# MaTouch_Devkit_Stepper_Driver_V1_1.net
KiCad netlist of a schematic drawn in EAGLE
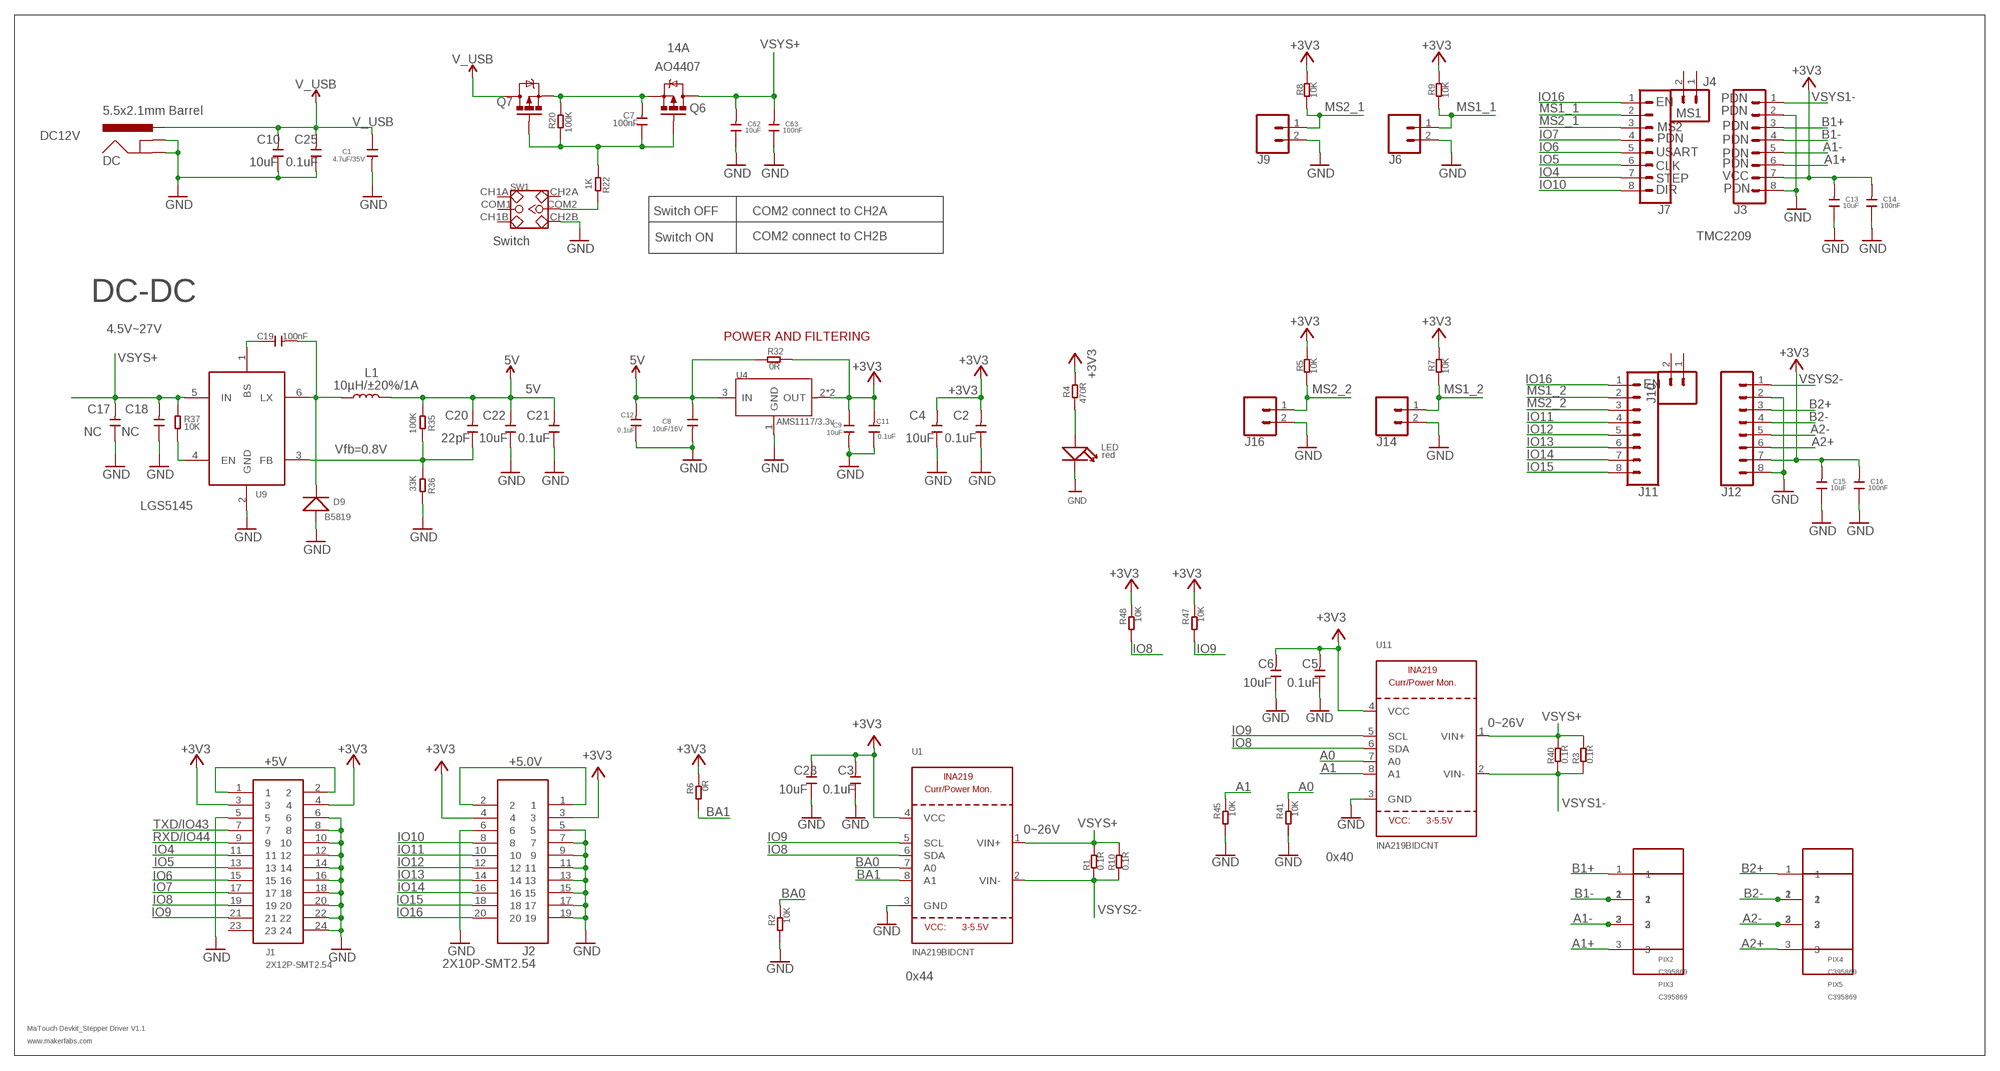
[diagram p0: schematic, sheet 1]

(export (version "E")
  (design (tool "Eeschema 10.0.6"))
  (components
    (comp (ref "C1")
      (value "4.7uF/35V")
      (footprint "eagle-import:0603")
      (libsource (lib "eagle-import") (part "C-0603"))
    )
    (comp (ref "C2")
      (value "0.1uF")
      (footprint "eagle-import:0603")
      (libsource (lib "eagle-import") (part "C-0603"))
    )
    (comp (ref "C3")
      (value "0.1uF")
      (footprint "eagle-import:0603")
      (libsource (lib "eagle-import") (part "C-0603"))
    )
    (comp (ref "C4")
      (value "10uF")
      (footprint "eagle-import:0603")
      (libsource (lib "eagle-import") (part "C-0603"))
    )
    (comp (ref "C5")
      (value "0.1uF")
      (footprint "eagle-import:0603")
      (libsource (lib "eagle-import") (part "C-0603"))
    )
    (comp (ref "C6")
      (value "10uF")
      (footprint "eagle-import:0603")
      (libsource (lib "eagle-import") (part "C-0603"))
    )
    (comp (ref "C7")
      (value "100nF")
      (footprint "eagle-import:0603")
      (libsource (lib "eagle-import") (part "C-0603"))
    )
    (comp (ref "C8")
      (value "10uF/16V")
      (footprint "eagle-import:0603")
      (libsource (lib "eagle-import") (part "C-0603"))
    )
    (comp (ref "C9")
      (value "10uF")
      (footprint "eagle-import:0603")
      (libsource (lib "eagle-import") (part "C-0603"))
    )
    (comp (ref "C10")
      (value "10uF")
      (footprint "eagle-import:0603")
      (libsource (lib "eagle-import") (part "C-0603"))
    )
    (comp (ref "C11")
      (value "0.1uF")
      (footprint "eagle-import:0603")
      (libsource (lib "eagle-import") (part "C-0603"))
    )
    (comp (ref "C12")
      (value "0.1uF")
      (footprint "eagle-import:0603")
      (libsource (lib "eagle-import") (part "C-0603"))
    )
    (comp (ref "C13")
      (value "10uF")
      (footprint "eagle-import:0603")
      (libsource (lib "eagle-import") (part "C-0603"))
    )
    (comp (ref "C14")
      (value "100nF")
      (footprint "eagle-import:0603")
      (libsource (lib "eagle-import") (part "C-0603"))
    )
    (comp (ref "C15")
      (value "10uF")
      (footprint "eagle-import:0603")
      (libsource (lib "eagle-import") (part "C-0603"))
    )
    (comp (ref "C16")
      (value "100nF")
      (footprint "eagle-import:0603")
      (libsource (lib "eagle-import") (part "C-0603"))
    )
    (comp (ref "C17")
      (value "NC")
      (footprint "eagle-import:0603")
      (libsource (lib "eagle-import") (part "C-0603"))
    )
    (comp (ref "C18")
      (value "NC")
      (footprint "eagle-import:0603")
      (libsource (lib "eagle-import") (part "C-0603"))
    )
    (comp (ref "C19")
      (value "100nF")
      (footprint "eagle-import:0603")
      (libsource (lib "eagle-import") (part "C-0603"))
    )
    (comp (ref "C20")
      (value "22pF")
      (footprint "eagle-import:0603")
      (libsource (lib "eagle-import") (part "C-0603"))
    )
    (comp (ref "C21")
      (value "0.1uF")
      (footprint "eagle-import:0603")
      (libsource (lib "eagle-import") (part "C-0603"))
    )
    (comp (ref "C22")
      (value "10uF")
      (footprint "eagle-import:0603")
      (libsource (lib "eagle-import") (part "C-0603"))
    )
    (comp (ref "C23")
      (value "10uF")
      (footprint "eagle-import:0603")
      (libsource (lib "eagle-import") (part "C-0603"))
    )
    (comp (ref "C25")
      (value "0.1uF")
      (footprint "eagle-import:0603")
      (libsource (lib "eagle-import") (part "C-0603"))
    )
    (comp (ref "C62")
      (value "10uF")
      (footprint "eagle-import:0603")
      (libsource (lib "eagle-import") (part "C-0603"))
    )
    (comp (ref "C63")
      (value "100nF")
      (footprint "eagle-import:0603")
      (libsource (lib "eagle-import") (part "C-0603"))
    )
    (comp (ref "D9")
      (value "B5819")
      (footprint "eagle-import:SOD123")
      (libsource (lib "eagle-import") (part "D'1206'"))
    )
    (comp (ref "DC")
      (value "5.5x2.1mm Barrel")
      (footprint "eagle-import:POWER_JACK_SMD")
      (libsource (lib "eagle-import") (part "POWER_JACKSMD"))
    )
    (comp (ref "J1")
      (value "2X12P-SMT2.54")
      (footprint "eagle-import:2X12P-SMT2.54")
      (libsource (lib "eagle-import") (part "2X12P-SMT2.54"))
    )
    (comp (ref "J2")
      (value "2X10P-SMT2.54")
      (footprint "eagle-import:2X10P-SMT2.54")
      (libsource (lib "eagle-import") (part "2X10P-SMT2.54"))
    )
    (comp (ref "J3")
      (value "CONN_08\"")
      (footprint "eagle-import:1X08")
      (fields (field (name "PROD_ID") "CONN-08438"))
      (libsource (lib "eagle-import") (part "CONN_08{dblquote}"))
    )
    (comp (ref "J4")
      (value "CONN_02LOCK")
      (footprint "eagle-import:1X02_LOCK")
      (libsource (lib "eagle-import") (part "CONN_02LOCK"))
    )
    (comp (ref "J6")
      (value "CONN_02LOCK")
      (footprint "eagle-import:1X02_LOCK")
      (libsource (lib "eagle-import") (part "CONN_02LOCK"))
    )
    (comp (ref "J7")
      (value "CONN_08\"")
      (footprint "eagle-import:1X08")
      (libsource (lib "eagle-import") (part "CONN_08{dblquote}"))
    )
    (comp (ref "J9")
      (value "CONN_02LOCK")
      (footprint "eagle-import:1X02_LOCK")
      (libsource (lib "eagle-import") (part "CONN_02LOCK"))
    )
    (comp (ref "J10")
      (value "CONN_02LOCK")
      (footprint "eagle-import:1X02_LOCK")
      (libsource (lib "eagle-import") (part "CONN_02LOCK"))
    )
    (comp (ref "J11")
      (value "CONN_08\"")
      (footprint "eagle-import:1X08")
      (libsource (lib "eagle-import") (part "CONN_08{dblquote}"))
    )
    (comp (ref "J12")
      (value "CONN_08\"")
      (footprint "eagle-import:1X08")
      (fields (field (name "PROD_ID") "CONN-08438"))
      (libsource (lib "eagle-import") (part "CONN_08{dblquote}"))
    )
    (comp (ref "J14")
      (value "CONN_02LOCK")
      (footprint "eagle-import:1X02_LOCK")
      (libsource (lib "eagle-import") (part "CONN_02LOCK"))
    )
    (comp (ref "J16")
      (value "CONN_02LOCK")
      (footprint "eagle-import:1X02_LOCK")
      (libsource (lib "eagle-import") (part "CONN_02LOCK"))
    )
    (comp (ref "L1")
      (value "10µH/±20%/1A")
      (footprint "eagle-import:SRN6045")
      (libsource (lib "eagle-import") (part "INDUCTOR-SRN6045-33UH"))
    )
    (comp (ref "LED")
      (value "red")
      (footprint "eagle-import:DISCRETE_LED-0603")
      (libsource (lib "eagle-import") (part "DISCRETE_LED0603"))
    )
    (comp (ref "PIX2")
      (value "C395869")
      (footprint "eagle-import:PIN_3P")
      (libsource (lib "eagle-import") (part "C395869"))
    )
    (comp (ref "PIX3")
      (value "C395869")
      (footprint "eagle-import:PIN_3P")
      (libsource (lib "eagle-import") (part "C395869"))
    )
    (comp (ref "PIX4")
      (value "C395869")
      (footprint "eagle-import:PIN_3P")
      (libsource (lib "eagle-import") (part "C395869"))
    )
    (comp (ref "PIX5")
      (value "C395869")
      (footprint "eagle-import:PIN_3P")
      (libsource (lib "eagle-import") (part "C395869"))
    )
    (comp (ref "Q6")
      (value "MOSFET-PCHANNELFDS6675")
      (footprint "eagle-import:SO08")
      (libsource (lib "eagle-import") (part "MOSFET-PCHANNELFDS6675"))
    )
    (comp (ref "Q7")
      (value "MOSFET-PCHANNELFDS6675")
      (footprint "eagle-import:SO08")
      (libsource (lib "eagle-import") (part "MOSFET-PCHANNELFDS6675"))
    )
    (comp (ref "R1")
      (value "0.1R")
      (footprint "eagle-import:DISCRETE_R2512")
      (libsource (lib "eagle-import") (part "DISCRETE_R-2512"))
    )
    (comp (ref "R2")
      (value "10K")
      (footprint "eagle-import:R0603")
      (libsource (lib "eagle-import") (part "R-0603"))
    )
    (comp (ref "R3")
      (value "0.1R")
      (footprint "eagle-import:DISCRETE_R2512")
      (libsource (lib "eagle-import") (part "DISCRETE_R-2512"))
    )
    (comp (ref "R4")
      (value "470R")
      (footprint "eagle-import:R0603")
      (libsource (lib "eagle-import") (part "R-0603"))
    )
    (comp (ref "R5")
      (value "10K")
      (footprint "eagle-import:R0603")
      (libsource (lib "eagle-import") (part "R-0603"))
    )
    (comp (ref "R6")
      (value "0R")
      (footprint "eagle-import:R0603")
      (libsource (lib "eagle-import") (part "R-0603"))
    )
    (comp (ref "R7")
      (value "10K")
      (footprint "eagle-import:R0603")
      (libsource (lib "eagle-import") (part "R-0603"))
    )
    (comp (ref "R8")
      (value "10K")
      (footprint "eagle-import:R0603")
      (libsource (lib "eagle-import") (part "R-0603"))
    )
    (comp (ref "R9")
      (value "10K")
      (footprint "eagle-import:R0603")
      (libsource (lib "eagle-import") (part "R-0603"))
    )
    (comp (ref "R10")
      (value "0.1R")
      (footprint "eagle-import:DISCRETE_R2512")
      (libsource (lib "eagle-import") (part "DISCRETE_R-2512"))
    )
    (comp (ref "R20")
      (value "100K")
      (footprint "eagle-import:R0603")
      (libsource (lib "eagle-import") (part "R-0603"))
    )
    (comp (ref "R22")
      (value "1K")
      (footprint "eagle-import:R0603")
      (libsource (lib "eagle-import") (part "R-0603"))
    )
    (comp (ref "R32")
      (value "0R")
      (footprint "eagle-import:R0603")
      (libsource (lib "eagle-import") (part "R-0603"))
    )
    (comp (ref "R35")
      (value "100K")
      (footprint "eagle-import:R0603")
      (libsource (lib "eagle-import") (part "R-0603"))
    )
    (comp (ref "R36")
      (value "33K")
      (footprint "eagle-import:R0603")
      (libsource (lib "eagle-import") (part "R-0603"))
    )
    (comp (ref "R37")
      (value "10K")
      (footprint "eagle-import:R0603")
      (libsource (lib "eagle-import") (part "R-0603"))
    )
    (comp (ref "R40")
      (value "0.1R")
      (footprint "eagle-import:DISCRETE_R2512")
      (libsource (lib "eagle-import") (part "DISCRETE_R-2512"))
    )
    (comp (ref "R41")
      (value "10K")
      (footprint "eagle-import:R0603")
      (libsource (lib "eagle-import") (part "R-0603"))
    )
    (comp (ref "R45")
      (value "10K")
      (footprint "eagle-import:R0603")
      (libsource (lib "eagle-import") (part "R-0603"))
    )
    (comp (ref "R47")
      (value "10K")
      (footprint "eagle-import:R0603")
      (libsource (lib "eagle-import") (part "R-0603"))
    )
    (comp (ref "R48")
      (value "10K")
      (footprint "eagle-import:R0603")
      (libsource (lib "eagle-import") (part "R-0603"))
    )
    (comp (ref "SW1")
      (value "SWITCH-2CH-6P'90D'")
      (footprint "eagle-import:6P-2CH-2.54-9.0X3.6-90D")
      (libsource (lib "eagle-import") (part "SWITCH-2CH-6P'90D'"))
    )
    (comp (ref "U1")
      (value "INA219BIDCNT")
      (footprint "eagle-import:SOT23-8")
      (libsource (lib "eagle-import") (part "INA219"))
    )
    (comp (ref "U4")
      (value "AMS1117/3.3v")
      (footprint "eagle-import:SOT89")
      (libsource (lib "eagle-import") (part "LD1117'SOT89'"))
    )
    (comp (ref "U9")
      (value "SY8201ABC")
      (footprint "eagle-import:SOT-23-6")
      (libsource (lib "eagle-import") (part "SY8201ABC"))
    )
    (comp (ref "U11")
      (value "INA219BIDCNT")
      (footprint "eagle-import:SOT23-8")
      (libsource (lib "eagle-import") (part "INA219"))
    )
  )
  (nets
    (net (code "1") (name "+3V3") (class "Default")
      (node (ref "C11") (pin "2") (pinfunction "2_2") (pintype "passive"))
      (node (ref "C13") (pin "2") (pinfunction "2_2") (pintype "passive"))
      (node (ref "C14") (pin "2") (pinfunction "2_2") (pintype "passive"))
      (node (ref "C15") (pin "2") (pinfunction "2_2") (pintype "passive"))
      (node (ref "C16") (pin "2") (pinfunction "2_2") (pintype "passive"))
      (node (ref "C2") (pin "2") (pinfunction "2_2") (pintype "passive"))
      (node (ref "C23") (pin "2") (pinfunction "2_2") (pintype "passive"))
      (node (ref "C3") (pin "2") (pinfunction "2_2") (pintype "passive"))
      (node (ref "C4") (pin "2") (pinfunction "2_2") (pintype "passive"))
      (node (ref "C5") (pin "2") (pinfunction "2_2") (pintype "passive"))
      (node (ref "C6") (pin "2") (pinfunction "2_2") (pintype "passive"))
      (node (ref "C9") (pin "1") (pinfunction "1_1") (pintype "passive"))
      (node (ref "J1") (pin "3") (pinfunction "3_3") (pintype "bidirectional"))
      (node (ref "J1") (pin "4") (pinfunction "4_4") (pintype "bidirectional"))
      (node (ref "J12") (pin "7") (pinfunction "7_7") (pintype "passive"))
      (node (ref "J2") (pin "3") (pinfunction "3_3") (pintype "bidirectional"))
      (node (ref "J2") (pin "4") (pinfunction "4_4") (pintype "bidirectional"))
      (node (ref "J3") (pin "7") (pinfunction "7_7") (pintype "passive"))
      (node (ref "R32") (pin "2") (pinfunction "2_2") (pintype "passive"))
      (node (ref "R4") (pin "2") (pinfunction "2_2") (pintype "passive"))
      (node (ref "R47") (pin "2") (pinfunction "2_2") (pintype "passive"))
      (node (ref "R48") (pin "2") (pinfunction "2_2") (pintype "passive"))
      (node (ref "R5") (pin "2") (pinfunction "2_2") (pintype "passive"))
      (node (ref "R6") (pin "2") (pinfunction "2_2") (pintype "passive"))
      (node (ref "R7") (pin "2") (pinfunction "2_2") (pintype "passive"))
      (node (ref "R8") (pin "2") (pinfunction "2_2") (pintype "passive"))
      (node (ref "R9") (pin "2") (pinfunction "2_2") (pintype "passive"))
      (node (ref "U1") (pin "4") (pinfunction "VCC_4") (pintype "power_in"))
      (node (ref "U11") (pin "4") (pinfunction "VCC_4") (pintype "power_in"))
      (node (ref "U4") (pin "2") (pinfunction "OUT_2") (pintype "bidirectional"))
      (node (ref "U4") (pin "4") (pinfunction "OUT_4") (pintype "bidirectional"))
    )
    (net (code "2") (name "/+5.0V") (class "Default")
      (node (ref "J2") (pin "1") (pinfunction "1_1") (pintype "bidirectional"))
      (node (ref "J2") (pin "2") (pinfunction "2_2") (pintype "bidirectional"))
    )
    (net (code "3") (name "/+5V") (class "Default")
      (node (ref "J1") (pin "1") (pinfunction "1_1") (pintype "bidirectional"))
      (node (ref "J1") (pin "2") (pinfunction "2_2") (pintype "bidirectional"))
    )
    (net (code "4") (name "/A0") (class "Default")
      (node (ref "R41") (pin "2") (pinfunction "2_2") (pintype "passive"))
      (node (ref "U11") (pin "7") (pinfunction "A0_7") (pintype "bidirectional"))
    )
    (net (code "5") (name "/A1") (class "Default")
      (node (ref "R45") (pin "2") (pinfunction "2_2") (pintype "passive"))
      (node (ref "U11") (pin "8") (pinfunction "A1_8") (pintype "bidirectional"))
    )
    (net (code "6") (name "/A1+") (class "Default")
      (node (ref "J3") (pin "6") (pinfunction "6_6") (pintype "passive"))
      (node (ref "PIX3") (pin "3") (pinfunction "3_3") (pintype "bidirectional"))
    )
    (net (code "7") (name "/A1-") (class "Default")
      (node (ref "J3") (pin "5") (pinfunction "5_5") (pintype "passive"))
      (node (ref "PIX2") (pin "3") (pinfunction "3_3") (pintype "bidirectional"))
      (node (ref "PIX3") (pin "2") (pinfunction "2_2") (pintype "bidirectional"))
    )
    (net (code "8") (name "/A2+") (class "Default")
      (node (ref "J12") (pin "6") (pinfunction "6_6") (pintype "passive"))
      (node (ref "PIX5") (pin "3") (pinfunction "3_3") (pintype "bidirectional"))
    )
    (net (code "9") (name "/A2-") (class "Default")
      (node (ref "J12") (pin "5") (pinfunction "5_5") (pintype "passive"))
      (node (ref "PIX4") (pin "3") (pinfunction "3_3") (pintype "bidirectional"))
      (node (ref "PIX5") (pin "2") (pinfunction "2_2") (pintype "bidirectional"))
    )
    (net (code "10") (name "/B1+") (class "Default")
      (node (ref "J3") (pin "3") (pinfunction "3_3") (pintype "passive"))
      (node (ref "PIX2") (pin "1") (pinfunction "1_1") (pintype "bidirectional"))
    )
    (net (code "11") (name "/B1-") (class "Default")
      (node (ref "J3") (pin "4") (pinfunction "4_4") (pintype "passive"))
      (node (ref "PIX2") (pin "2") (pinfunction "2_2") (pintype "bidirectional"))
      (node (ref "PIX3") (pin "1") (pinfunction "1_1") (pintype "bidirectional"))
    )
    (net (code "12") (name "/B2+") (class "Default")
      (node (ref "J12") (pin "3") (pinfunction "3_3") (pintype "passive"))
      (node (ref "PIX4") (pin "1") (pinfunction "1_1") (pintype "bidirectional"))
    )
    (net (code "13") (name "/B2-") (class "Default")
      (node (ref "J12") (pin "4") (pinfunction "4_4") (pintype "passive"))
      (node (ref "PIX4") (pin "2") (pinfunction "2_2") (pintype "bidirectional"))
      (node (ref "PIX5") (pin "1") (pinfunction "1_1") (pintype "bidirectional"))
    )
    (net (code "14") (name "/BA0") (class "Default")
      (node (ref "R2") (pin "2") (pinfunction "2_2") (pintype "passive"))
      (node (ref "U1") (pin "7") (pinfunction "A0_7") (pintype "bidirectional"))
    )
    (net (code "15") (name "/BA1") (class "Default")
      (node (ref "R6") (pin "1") (pinfunction "1_1") (pintype "passive"))
      (node (ref "U1") (pin "8") (pinfunction "A1_8") (pintype "bidirectional"))
    )
    (net (code "16") (name "/IO4") (class "Default")
      (node (ref "J1") (pin "11") (pinfunction "11_11") (pintype "bidirectional"))
      (node (ref "J7") (pin "7") (pinfunction "7_7") (pintype "passive"))
    )
    (net (code "17") (name "/IO5") (class "Default")
      (node (ref "J1") (pin "13") (pinfunction "13_13") (pintype "bidirectional"))
      (node (ref "J7") (pin "6") (pinfunction "6_6") (pintype "passive"))
    )
    (net (code "18") (name "/IO6") (class "Default")
      (node (ref "J1") (pin "15") (pinfunction "15_15") (pintype "bidirectional"))
      (node (ref "J7") (pin "5") (pinfunction "5_5") (pintype "passive"))
    )
    (net (code "19") (name "/IO7") (class "Default")
      (node (ref "J1") (pin "17") (pinfunction "17_17") (pintype "bidirectional"))
      (node (ref "J7") (pin "4") (pinfunction "4_4") (pintype "passive"))
    )
    (net (code "20") (name "/IO8") (class "Default")
      (node (ref "J1") (pin "19") (pinfunction "19_19") (pintype "bidirectional"))
      (node (ref "R48") (pin "1") (pinfunction "1_1") (pintype "passive"))
      (node (ref "U1") (pin "6") (pinfunction "SDA_6") (pintype "bidirectional"))
      (node (ref "U11") (pin "6") (pinfunction "SDA_6") (pintype "bidirectional"))
    )
    (net (code "21") (name "/IO9") (class "Default")
      (node (ref "J1") (pin "21") (pinfunction "21_21") (pintype "bidirectional"))
      (node (ref "R47") (pin "1") (pinfunction "1_1") (pintype "passive"))
      (node (ref "U1") (pin "5") (pinfunction "SCL_5") (pintype "bidirectional"))
      (node (ref "U11") (pin "5") (pinfunction "SCL_5") (pintype "bidirectional"))
    )
    (net (code "22") (name "/IO10") (class "Default")
      (node (ref "J2") (pin "8") (pinfunction "8_8") (pintype "bidirectional"))
      (node (ref "J7") (pin "8") (pinfunction "8_8") (pintype "passive"))
    )
    (net (code "23") (name "/IO11") (class "Default")
      (node (ref "J11") (pin "4") (pinfunction "4_4") (pintype "passive"))
      (node (ref "J2") (pin "10") (pinfunction "10_10") (pintype "bidirectional"))
    )
    (net (code "24") (name "/IO12") (class "Default")
      (node (ref "J11") (pin "5") (pinfunction "5_5") (pintype "passive"))
      (node (ref "J2") (pin "12") (pinfunction "12_12") (pintype "bidirectional"))
    )
    (net (code "25") (name "/IO13") (class "Default")
      (node (ref "J11") (pin "6") (pinfunction "6_6") (pintype "passive"))
      (node (ref "J2") (pin "14") (pinfunction "14_14") (pintype "bidirectional"))
    )
    (net (code "26") (name "/IO14") (class "Default")
      (node (ref "J11") (pin "7") (pinfunction "7_7") (pintype "passive"))
      (node (ref "J2") (pin "16") (pinfunction "16_16") (pintype "bidirectional"))
    )
    (net (code "27") (name "/IO15") (class "Default")
      (node (ref "J11") (pin "8") (pinfunction "8_8") (pintype "passive"))
      (node (ref "J2") (pin "18") (pinfunction "18_18") (pintype "bidirectional"))
    )
    (net (code "28") (name "/IO16") (class "Default")
      (node (ref "J11") (pin "1") (pinfunction "1_1") (pintype "passive"))
      (node (ref "J2") (pin "20") (pinfunction "20_20") (pintype "bidirectional"))
      (node (ref "J7") (pin "1") (pinfunction "1_1") (pintype "passive"))
    )
    (net (code "29") (name "/MS1_1") (class "Default")
      (node (ref "J6") (pin "1") (pinfunction "1_1") (pintype "passive"))
      (node (ref "J7") (pin "2") (pinfunction "2_2") (pintype "passive"))
      (node (ref "R9") (pin "1") (pinfunction "1_1") (pintype "passive"))
    )
    (net (code "30") (name "/MS1_2") (class "Default")
      (node (ref "J11") (pin "2") (pinfunction "2_2") (pintype "passive"))
      (node (ref "J14") (pin "1") (pinfunction "1_1") (pintype "passive"))
      (node (ref "R7") (pin "1") (pinfunction "1_1") (pintype "passive"))
    )
    (net (code "31") (name "/MS2_1") (class "Default")
      (node (ref "J7") (pin "3") (pinfunction "3_3") (pintype "passive"))
      (node (ref "J9") (pin "1") (pinfunction "1_1") (pintype "passive"))
      (node (ref "R8") (pin "1") (pinfunction "1_1") (pintype "passive"))
    )
    (net (code "32") (name "/MS2_2") (class "Default")
      (node (ref "J11") (pin "3") (pinfunction "3_3") (pintype "passive"))
      (node (ref "J16") (pin "1") (pinfunction "1_1") (pintype "passive"))
      (node (ref "R5") (pin "1") (pinfunction "1_1") (pintype "passive"))
    )
    (net (code "33") (name "/RXD{slash}IO44") (class "Default")
      (node (ref "J1") (pin "9") (pinfunction "9_9") (pintype "bidirectional"))
    )
    (net (code "34") (name "/TXD{slash}IO43") (class "Default")
      (node (ref "J1") (pin "7") (pinfunction "7_7") (pintype "bidirectional"))
    )
    (net (code "35") (name "/VSYS+") (class "Default")
      (node (ref "C17") (pin "2") (pinfunction "2_2") (pintype "passive"))
      (node (ref "C18") (pin "2") (pinfunction "2_2") (pintype "passive"))
      (node (ref "C62") (pin "2") (pinfunction "2_2") (pintype "passive"))
      (node (ref "C63") (pin "2") (pinfunction "2_2") (pintype "passive"))
      (node (ref "Q6") (pin "5") (pinfunction "D_5") (pintype "passive"))
      (node (ref "Q6") (pin "6") (pinfunction "D_6") (pintype "passive"))
      (node (ref "Q6") (pin "7") (pinfunction "D_7") (pintype "passive"))
      (node (ref "Q6") (pin "8") (pinfunction "D_8") (pintype "passive"))
      (node (ref "R1") (pin "2") (pinfunction "2_2") (pintype "passive"))
      (node (ref "R10") (pin "2") (pinfunction "2_2") (pintype "passive"))
      (node (ref "R3") (pin "2") (pinfunction "2_2") (pintype "passive"))
      (node (ref "R37") (pin "1") (pinfunction "1_1") (pintype "passive"))
      (node (ref "R40") (pin "2") (pinfunction "2_2") (pintype "passive"))
      (node (ref "U1") (pin "1") (pinfunction "VIN+_1") (pintype "bidirectional"))
      (node (ref "U11") (pin "1") (pinfunction "VIN+_1") (pintype "bidirectional"))
      (node (ref "U9") (pin "5") (pinfunction "IN_5") (pintype "bidirectional"))
    )
    (net (code "36") (name "/VSYS1-") (class "Default")
      (node (ref "J3") (pin "1") (pinfunction "1_1") (pintype "passive"))
      (node (ref "R3") (pin "1") (pinfunction "1_1") (pintype "passive"))
      (node (ref "R40") (pin "1") (pinfunction "1_1") (pintype "passive"))
      (node (ref "U11") (pin "2") (pinfunction "VIN-_2") (pintype "bidirectional"))
    )
    (net (code "37") (name "/VSYS2-") (class "Default")
      (node (ref "J12") (pin "1") (pinfunction "1_1") (pintype "passive"))
      (node (ref "R1") (pin "1") (pinfunction "1_1") (pintype "passive"))
      (node (ref "R10") (pin "1") (pinfunction "1_1") (pintype "passive"))
      (node (ref "U1") (pin "2") (pinfunction "VIN-_2") (pintype "bidirectional"))
    )
    (net (code "38") (name "5V") (class "Default")
      (node (ref "C12") (pin "2") (pinfunction "2_2") (pintype "passive"))
      (node (ref "C20") (pin "2") (pinfunction "2_2") (pintype "passive"))
      (node (ref "C21") (pin "2") (pinfunction "2_2") (pintype "passive"))
      (node (ref "C22") (pin "2") (pinfunction "2_2") (pintype "passive"))
      (node (ref "C8") (pin "1") (pinfunction "1_1") (pintype "passive"))
      (node (ref "L1") (pin "2") (pinfunction "2_2") (pintype "passive"))
      (node (ref "R32") (pin "1") (pinfunction "1_1") (pintype "passive"))
      (node (ref "R35") (pin "1") (pinfunction "1_1") (pintype "passive"))
      (node (ref "U4") (pin "3") (pinfunction "IN_3") (pintype "bidirectional"))
    )
    (net (code "39") (name "GND") (class "Default")
      (node (ref "C1") (pin "2") (pinfunction "2_2") (pintype "passive"))
      (node (ref "C10") (pin "1") (pinfunction "1_1") (pintype "passive"))
      (node (ref "C11") (pin "1") (pinfunction "1_1") (pintype "passive"))
      (node (ref "C12") (pin "1") (pinfunction "1_1") (pintype "passive"))
      (node (ref "C13") (pin "1") (pinfunction "1_1") (pintype "passive"))
      (node (ref "C14") (pin "1") (pinfunction "1_1") (pintype "passive"))
      (node (ref "C15") (pin "1") (pinfunction "1_1") (pintype "passive"))
      (node (ref "C16") (pin "1") (pinfunction "1_1") (pintype "passive"))
      (node (ref "C17") (pin "1") (pinfunction "1_1") (pintype "passive"))
      (node (ref "C18") (pin "1") (pinfunction "1_1") (pintype "passive"))
      (node (ref "C2") (pin "1") (pinfunction "1_1") (pintype "passive"))
      (node (ref "C21") (pin "1") (pinfunction "1_1") (pintype "passive"))
      (node (ref "C22") (pin "1") (pinfunction "1_1") (pintype "passive"))
      (node (ref "C23") (pin "1") (pinfunction "1_1") (pintype "passive"))
      (node (ref "C25") (pin "1") (pinfunction "1_1") (pintype "passive"))
      (node (ref "C3") (pin "1") (pinfunction "1_1") (pintype "passive"))
      (node (ref "C4") (pin "1") (pinfunction "1_1") (pintype "passive"))
      (node (ref "C5") (pin "1") (pinfunction "1_1") (pintype "passive"))
      (node (ref "C6") (pin "1") (pinfunction "1_1") (pintype "passive"))
      (node (ref "C62") (pin "1") (pinfunction "1_1") (pintype "passive"))
      (node (ref "C63") (pin "1") (pinfunction "1_1") (pintype "passive"))
      (node (ref "C8") (pin "2") (pinfunction "2_2") (pintype "passive"))
      (node (ref "C9") (pin "2") (pinfunction "2_2") (pintype "passive"))
      (node (ref "D9") (pin "+") (pinfunction "+_+") (pintype "passive"))
      (node (ref "DC") (pin "GND") (pinfunction "GNDBREAK_GND") (pintype "bidirectional"))
      (node (ref "DC") (pin "P$4") (pinfunction "GND_P$4") (pintype "bidirectional"))
      (node (ref "J1") (pin "10") (pinfunction "10_10") (pintype "bidirectional"))
      (node (ref "J1") (pin "12") (pinfunction "12_12") (pintype "bidirectional"))
      (node (ref "J1") (pin "14") (pinfunction "14_14") (pintype "bidirectional"))
      (node (ref "J1") (pin "16") (pinfunction "16_16") (pintype "bidirectional"))
      (node (ref "J1") (pin "18") (pinfunction "18_18") (pintype "bidirectional"))
      (node (ref "J1") (pin "20") (pinfunction "20_20") (pintype "bidirectional"))
      (node (ref "J1") (pin "22") (pinfunction "22_22") (pintype "bidirectional"))
      (node (ref "J1") (pin "24") (pinfunction "24_24") (pintype "bidirectional"))
      (node (ref "J1") (pin "5") (pinfunction "5_5") (pintype "bidirectional"))
      (node (ref "J1") (pin "6") (pinfunction "6_6") (pintype "bidirectional"))
      (node (ref "J1") (pin "8") (pinfunction "8_8") (pintype "bidirectional"))
      (node (ref "J12") (pin "2") (pinfunction "2_2") (pintype "passive"))
      (node (ref "J12") (pin "8") (pinfunction "8_8") (pintype "passive"))
      (node (ref "J14") (pin "2") (pinfunction "2_2") (pintype "passive"))
      (node (ref "J16") (pin "2") (pinfunction "2_2") (pintype "passive"))
      (node (ref "J2") (pin "11") (pinfunction "11_11") (pintype "bidirectional"))
      (node (ref "J2") (pin "13") (pinfunction "13_13") (pintype "bidirectional"))
      (node (ref "J2") (pin "15") (pinfunction "15_15") (pintype "bidirectional"))
      (node (ref "J2") (pin "17") (pinfunction "17_17") (pintype "bidirectional"))
      (node (ref "J2") (pin "19") (pinfunction "19_19") (pintype "bidirectional"))
      (node (ref "J2") (pin "5") (pinfunction "5_5") (pintype "bidirectional"))
      (node (ref "J2") (pin "6") (pinfunction "6_6") (pintype "bidirectional"))
      (node (ref "J2") (pin "7") (pinfunction "7_7") (pintype "bidirectional"))
      (node (ref "J2") (pin "9") (pinfunction "9_9") (pintype "bidirectional"))
      (node (ref "J3") (pin "2") (pinfunction "2_2") (pintype "passive"))
      (node (ref "J3") (pin "8") (pinfunction "8_8") (pintype "passive"))
      (node (ref "J6") (pin "2") (pinfunction "2_2") (pintype "passive"))
      (node (ref "J9") (pin "2") (pinfunction "2_2") (pintype "passive"))
      (node (ref "LED") (pin "-") (pinfunction "-_-") (pintype "passive"))
      (node (ref "R2") (pin "1") (pinfunction "1_1") (pintype "passive"))
      (node (ref "R36") (pin "2") (pinfunction "2_2") (pintype "passive"))
      (node (ref "R41") (pin "1") (pinfunction "1_1") (pintype "passive"))
      (node (ref "R45") (pin "1") (pinfunction "1_1") (pintype "passive"))
      (node (ref "SW1") (pin "CH2B") (pinfunction "CH2B_CH2B") (pintype "bidirectional"))
      (node (ref "U1") (pin "3") (pinfunction "GND_3") (pintype "power_in"))
      (node (ref "U11") (pin "3") (pinfunction "GND_3") (pintype "power_in"))
      (node (ref "U4") (pin "1") (pinfunction "GND_1") (pintype "bidirectional"))
      (node (ref "U9") (pin "2") (pinfunction "GND_2") (pintype "bidirectional"))
    )
    (net (code "40") (name "Net-(C7-Pad2)") (class "Default")
      (node (ref "C7") (pin "2") (pinfunction "2_2") (pintype "passive"))
      (node (ref "Q6") (pin "1") (pinfunction "S_1") (pintype "passive"))
      (node (ref "Q6") (pin "2") (pinfunction "S_2") (pintype "passive"))
      (node (ref "Q6") (pin "3") (pinfunction "S_3") (pintype "passive"))
      (node (ref "Q7") (pin "1") (pinfunction "S_1") (pintype "passive"))
      (node (ref "Q7") (pin "2") (pinfunction "S_2") (pintype "passive"))
      (node (ref "Q7") (pin "3") (pinfunction "S_3") (pintype "passive"))
      (node (ref "R20") (pin "1") (pinfunction "1_1") (pintype "passive"))
    )
    (net (code "41") (name "Net-(LED-Pad+)") (class "Default")
      (node (ref "LED") (pin "+") (pinfunction "+_+") (pintype "passive"))
      (node (ref "R4") (pin "1") (pinfunction "1_1") (pintype "passive"))
    )
    (net (code "42") (name "Net-(Q6-G)") (class "Default")
      (node (ref "C7") (pin "1") (pinfunction "1_1") (pintype "passive"))
      (node (ref "Q6") (pin "4") (pinfunction "G_4") (pintype "passive"))
      (node (ref "Q7") (pin "4") (pinfunction "G_4") (pintype "passive"))
      (node (ref "R20") (pin "2") (pinfunction "2_2") (pintype "passive"))
      (node (ref "R22") (pin "2") (pinfunction "2_2") (pintype "passive"))
    )
    (net (code "43") (name "Net-(R22-Pad1)") (class "Default")
      (node (ref "R22") (pin "1") (pinfunction "1_1") (pintype "passive"))
      (node (ref "SW1") (pin "COM2") (pinfunction "COM2_COM2") (pintype "bidirectional"))
    )
    (net (code "44") (name "Net-(U9-BS)") (class "Default")
      (node (ref "C19") (pin "1") (pinfunction "1_1") (pintype "passive"))
      (node (ref "U9") (pin "1") (pinfunction "BS_1") (pintype "bidirectional"))
    )
    (net (code "45") (name "Net-(U9-EN)") (class "Default")
      (node (ref "R37") (pin "2") (pinfunction "2_2") (pintype "passive"))
      (node (ref "U9") (pin "4") (pinfunction "EN_4") (pintype "bidirectional"))
    )
    (net (code "46") (name "Net-(U9-FB)") (class "Default")
      (node (ref "C20") (pin "1") (pinfunction "1_1") (pintype "passive"))
      (node (ref "R35") (pin "2") (pinfunction "2_2") (pintype "passive"))
      (node (ref "R36") (pin "1") (pinfunction "1_1") (pintype "passive"))
      (node (ref "U9") (pin "3") (pinfunction "FB_3") (pintype "bidirectional"))
    )
    (net (code "47") (name "Net-(U9-LX)") (class "Default")
      (node (ref "C19") (pin "2") (pinfunction "2_2") (pintype "passive"))
      (node (ref "D9") (pin "-") (pinfunction "-_-") (pintype "passive"))
      (node (ref "L1") (pin "1") (pinfunction "1_1") (pintype "passive"))
      (node (ref "U9") (pin "6") (pinfunction "LX_6") (pintype "bidirectional"))
    )
    (net (code "48") (name "V_USB") (class "Default")
      (node (ref "C1") (pin "1") (pinfunction "1_1") (pintype "passive"))
      (node (ref "C10") (pin "2") (pinfunction "2_2") (pintype "passive"))
      (node (ref "C25") (pin "2") (pinfunction "2_2") (pintype "passive"))
      (node (ref "DC") (pin "VIN0") (pinfunction "PWR_VIN0") (pintype "bidirectional"))
      (node (ref "Q7") (pin "5") (pinfunction "D_5") (pintype "passive"))
      (node (ref "Q7") (pin "6") (pinfunction "D_6") (pintype "passive"))
      (node (ref "Q7") (pin "7") (pinfunction "D_7") (pintype "passive"))
      (node (ref "Q7") (pin "8") (pinfunction "D_8") (pintype "passive"))
    )
    (net (code "49") (name "unconnected-(J1-Pad23)") (class "Default")
      (node (ref "J1") (pin "23") (pinfunction "23_23") (pintype "bidirectional"))
    )
    (net (code "50") (name "unconnected-(J4-Pad1)") (class "Default")
      (node (ref "J4") (pin "1") (pinfunction "1_1") (pintype "passive"))
    )
    (net (code "51") (name "unconnected-(J4-Pad2)") (class "Default")
      (node (ref "J4") (pin "2") (pinfunction "2_2") (pintype "passive"))
    )
    (net (code "52") (name "unconnected-(J10-Pad1)") (class "Default")
      (node (ref "J10") (pin "1") (pinfunction "1_1") (pintype "passive"))
    )
    (net (code "53") (name "unconnected-(J10-Pad2)") (class "Default")
      (node (ref "J10") (pin "2") (pinfunction "2_2") (pintype "passive"))
    )
    (net (code "54") (name "unconnected-(SW1-PadCH1A)") (class "Default")
      (node (ref "SW1") (pin "CH1A") (pinfunction "CH1A_CH1A") (pintype "bidirectional"))
    )
    (net (code "55") (name "unconnected-(SW1-PadCH1B)") (class "Default")
      (node (ref "SW1") (pin "CH1B") (pinfunction "CH1B_CH1B") (pintype "bidirectional"))
    )
    (net (code "56") (name "unconnected-(SW1-PadCH2A)") (class "Default")
      (node (ref "SW1") (pin "CH2A") (pinfunction "CH2A_CH2A") (pintype "bidirectional"))
    )
    (net (code "57") (name "unconnected-(SW1-PadCOM1)") (class "Default")
      (node (ref "SW1") (pin "COM1") (pinfunction "COM1_COM1") (pintype "bidirectional"))
    )
  )
)
